# Filla_GPS_2015.net
KiCad netlist of a schematic drawn in EAGLE
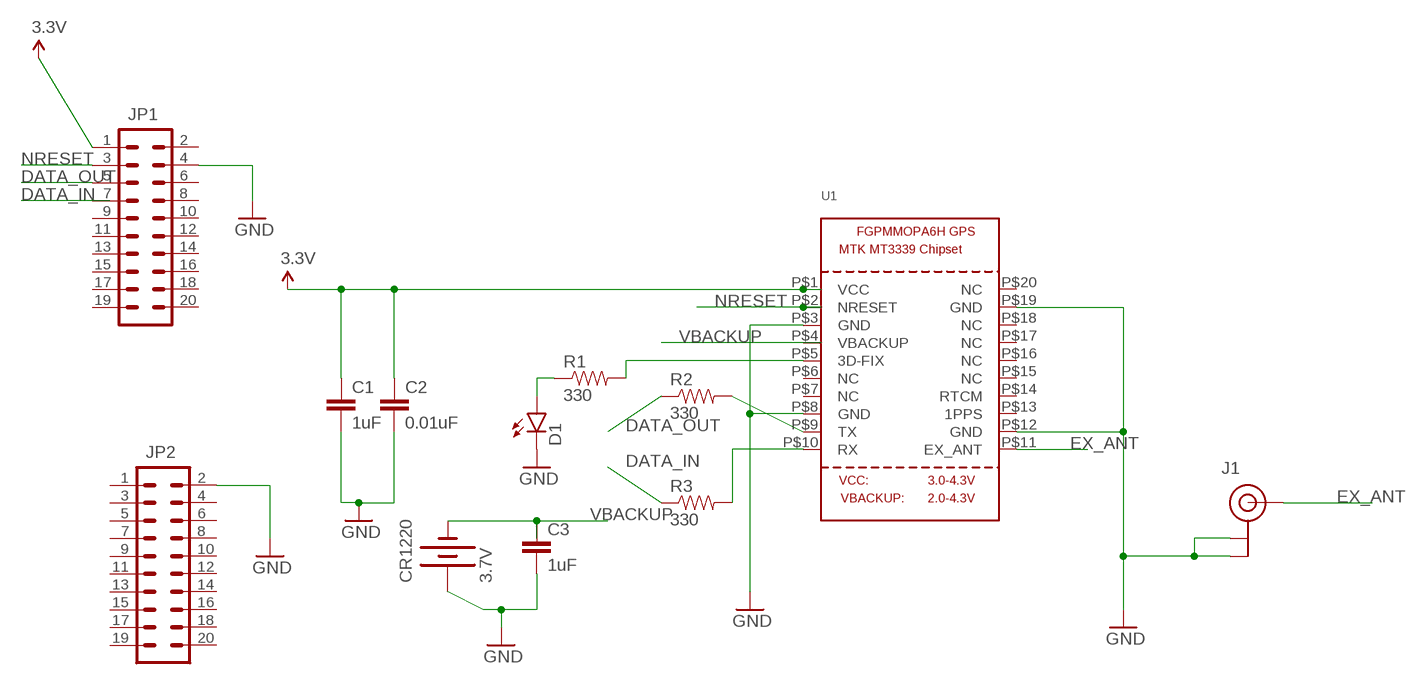
[diagram p0: schematic, sheet 1]

(export (version "E")
  (design (tool "Eeschema 10.0.6"))
  (components
    (comp (ref "C1")
      (value "1uF")
      (footprint "eagle-import:1206")
      (libsource (lib "eagle-import") (part "CAP1206"))
    )
    (comp (ref "C2")
      (value "0.01uF")
      (footprint "eagle-import:1206")
      (libsource (lib "eagle-import") (part "CAP1206"))
    )
    (comp (ref "C3")
      (value "1uF")
      (footprint "eagle-import:1206")
      (libsource (lib "eagle-import") (part "CAP1206"))
    )
    (comp (ref "CR1220")
      (value "3.7V")
      (footprint "eagle-import:BATTCON_12MM")
      (libsource (lib "eagle-import") (part "BATTERY12MM"))
    )
    (comp (ref "D1")
      (value "LED1206")
      (footprint "eagle-import:LED-1206")
      (libsource (lib "eagle-import") (part "LED1206"))
    )
    (comp (ref "J1")
      (value "U.FL")
      (footprint "eagle-import:U.FL")
      (libsource (lib "eagle-import") (part "U.FL"))
    )
    (comp (ref "JP1")
      (value "M10X2")
      (footprint "eagle-import:2X10")
      (libsource (lib "eagle-import") (part "M10X2"))
    )
    (comp (ref "JP2")
      (value "M10X2")
      (footprint "eagle-import:2X10")
      (libsource (lib "eagle-import") (part "M10X2"))
    )
    (comp (ref "R1")
      (value "330")
      (footprint "eagle-import:1206")
      (libsource (lib "eagle-import") (part "RESISTOR1206"))
    )
    (comp (ref "R2")
      (value "330")
      (footprint "eagle-import:1206")
      (libsource (lib "eagle-import") (part "RESISTOR1206"))
    )
    (comp (ref "R3")
      (value "330")
      (footprint "eagle-import:1206")
      (libsource (lib "eagle-import") (part "RESISTOR1206"))
    )
    (comp (ref "U1")
      (value "GPS_FGPMMOPA6H")
      (footprint "eagle-import:FGPMMOPA6H")
      (libsource (lib "eagle-import") (part "GPS_FGPMMOPA6H"))
    )
  )
  (nets
    (net (code "1") (name "/DATA_IN") (class "Default")
      (node (ref "R3") (pin "1") (pinfunction "1_1") (pintype "passive"))
    )
    (net (code "2") (name "/DATA_OUT") (class "Default")
      (node (ref "JP1") (pin "5") (pinfunction "5_5") (pintype "passive"))
      (node (ref "R2") (pin "1") (pinfunction "1_1") (pintype "passive"))
    )
    (net (code "3") (name "/EX_ANT") (class "Default")
      (node (ref "J1") (pin "P$3") (pinfunction "SIGNAL_P$3") (pintype "bidirectional"))
      (node (ref "U1") (pin "P$11") (pinfunction "EX_ANT_P$11") (pintype "bidirectional"))
    )
    (net (code "4") (name "/NRESET") (class "Default")
      (node (ref "JP1") (pin "3") (pinfunction "3_3") (pintype "passive"))
      (node (ref "U1") (pin "P$2") (pinfunction "NRESET_P$2") (pintype "bidirectional"))
    )
    (net (code "5") (name "/VBACKUP") (class "Default")
      (node (ref "C3") (pin "1") (pinfunction "1_1") (pintype "passive"))
      (node (ref "CR1220") (pin "GND") (pinfunction "-_GND") (pintype "power_in"))
    )
    (net (code "6") (name "3.3V") (class "Default")
      (node (ref "C1") (pin "1") (pinfunction "1_1") (pintype "passive"))
      (node (ref "C2") (pin "1") (pinfunction "1_1") (pintype "passive"))
      (node (ref "JP1") (pin "1") (pinfunction "1_1") (pintype "passive"))
      (node (ref "U1") (pin "P$1") (pinfunction "VCC_P$1") (pintype "bidirectional"))
    )
    (net (code "7") (name "GND") (class "Default")
      (node (ref "C1") (pin "2") (pinfunction "2_2") (pintype "passive"))
      (node (ref "C2") (pin "2") (pinfunction "2_2") (pintype "passive"))
      (node (ref "C3") (pin "2") (pinfunction "2_2") (pintype "passive"))
      (node (ref "CR1220") (pin "PWR@1") (pinfunction "+_PWR@1") (pintype "power_in"))
      (node (ref "D1") (pin "C") (pinfunction "C_C") (pintype "passive"))
      (node (ref "J1") (pin "P$1") (pinfunction "GND_P$1") (pintype "bidirectional"))
      (node (ref "J1") (pin "P$2") (pinfunction "GND_P$2") (pintype "bidirectional"))
      (node (ref "JP1") (pin "4") (pinfunction "4_4") (pintype "passive"))
      (node (ref "JP2") (pin "2") (pinfunction "2_2") (pintype "passive"))
      (node (ref "U1") (pin "P$12") (pinfunction "GND_P$12") (pintype "bidirectional"))
      (node (ref "U1") (pin "P$19") (pinfunction "GND_P$19") (pintype "bidirectional"))
      (node (ref "U1") (pin "P$3") (pinfunction "GND_P$3") (pintype "bidirectional"))
      (node (ref "U1") (pin "P$8") (pinfunction "GND_P$8") (pintype "bidirectional"))
    )
    (net (code "8") (name "Net-(D1-PadA)") (class "Default")
      (node (ref "D1") (pin "A") (pinfunction "A_A") (pintype "passive"))
      (node (ref "R1") (pin "1") (pinfunction "1_1") (pintype "passive"))
    )
    (net (code "9") (name "Net-(U1-3D-FIX)") (class "Default")
      (node (ref "R1") (pin "2") (pinfunction "2_2") (pintype "passive"))
      (node (ref "U1") (pin "P$5") (pinfunction "3D-FIX_P$5") (pintype "bidirectional"))
    )
    (net (code "10") (name "Net-(U1-RX)") (class "Default")
      (node (ref "R3") (pin "2") (pinfunction "2_2") (pintype "passive"))
      (node (ref "U1") (pin "P$10") (pinfunction "RX_P$10") (pintype "bidirectional"))
    )
    (net (code "11") (name "Net-(U1-TX)") (class "Default")
      (node (ref "R2") (pin "2") (pinfunction "2_2") (pintype "passive"))
      (node (ref "U1") (pin "P$9") (pinfunction "TX_P$9") (pintype "bidirectional"))
    )
    (net (code "12") (name "unconnected-(JP1-Pad2)") (class "Default")
      (node (ref "JP1") (pin "2") (pinfunction "2_2") (pintype "passive"))
    )
    (net (code "13") (name "unconnected-(JP1-Pad6)") (class "Default")
      (node (ref "JP1") (pin "6") (pinfunction "6_6") (pintype "passive"))
    )
    (net (code "14") (name "unconnected-(JP1-Pad7)") (class "Default")
      (node (ref "JP1") (pin "7") (pinfunction "7_7") (pintype "passive"))
    )
    (net (code "15") (name "unconnected-(JP1-Pad8)") (class "Default")
      (node (ref "JP1") (pin "8") (pinfunction "8_8") (pintype "passive"))
    )
    (net (code "16") (name "unconnected-(JP1-Pad9)") (class "Default")
      (node (ref "JP1") (pin "9") (pinfunction "9_9") (pintype "passive"))
    )
    (net (code "17") (name "unconnected-(JP1-Pad10)") (class "Default")
      (node (ref "JP1") (pin "10") (pinfunction "10_10") (pintype "passive"))
    )
    (net (code "18") (name "unconnected-(JP1-Pad11)") (class "Default")
      (node (ref "JP1") (pin "11") (pinfunction "11_11") (pintype "passive"))
    )
    (net (code "19") (name "unconnected-(JP1-Pad12)") (class "Default")
      (node (ref "JP1") (pin "12") (pinfunction "12_12") (pintype "passive"))
    )
    (net (code "20") (name "unconnected-(JP1-Pad13)") (class "Default")
      (node (ref "JP1") (pin "13") (pinfunction "13_13") (pintype "passive"))
    )
    (net (code "21") (name "unconnected-(JP1-Pad14)") (class "Default")
      (node (ref "JP1") (pin "14") (pinfunction "14_14") (pintype "passive"))
    )
    (net (code "22") (name "unconnected-(JP1-Pad15)") (class "Default")
      (node (ref "JP1") (pin "15") (pinfunction "15_15") (pintype "passive"))
    )
    (net (code "23") (name "unconnected-(JP1-Pad16)") (class "Default")
      (node (ref "JP1") (pin "16") (pinfunction "16_16") (pintype "passive"))
    )
    (net (code "24") (name "unconnected-(JP1-Pad17)") (class "Default")
      (node (ref "JP1") (pin "17") (pinfunction "17_17") (pintype "passive"))
    )
    (net (code "25") (name "unconnected-(JP1-Pad18)") (class "Default")
      (node (ref "JP1") (pin "18") (pinfunction "18_18") (pintype "passive"))
    )
    (net (code "26") (name "unconnected-(JP1-Pad19)") (class "Default")
      (node (ref "JP1") (pin "19") (pinfunction "19_19") (pintype "passive"))
    )
    (net (code "27") (name "unconnected-(JP1-Pad20)") (class "Default")
      (node (ref "JP1") (pin "20") (pinfunction "20_20") (pintype "passive"))
    )
    (net (code "28") (name "unconnected-(JP2-Pad1)") (class "Default")
      (node (ref "JP2") (pin "1") (pinfunction "1_1") (pintype "passive"))
    )
    (net (code "29") (name "unconnected-(JP2-Pad3)") (class "Default")
      (node (ref "JP2") (pin "3") (pinfunction "3_3") (pintype "passive"))
    )
    (net (code "30") (name "unconnected-(JP2-Pad4)") (class "Default")
      (node (ref "JP2") (pin "4") (pinfunction "4_4") (pintype "passive"))
    )
    (net (code "31") (name "unconnected-(JP2-Pad5)") (class "Default")
      (node (ref "JP2") (pin "5") (pinfunction "5_5") (pintype "passive"))
    )
    (net (code "32") (name "unconnected-(JP2-Pad6)") (class "Default")
      (node (ref "JP2") (pin "6") (pinfunction "6_6") (pintype "passive"))
    )
    (net (code "33") (name "unconnected-(JP2-Pad7)") (class "Default")
      (node (ref "JP2") (pin "7") (pinfunction "7_7") (pintype "passive"))
    )
    (net (code "34") (name "unconnected-(JP2-Pad8)") (class "Default")
      (node (ref "JP2") (pin "8") (pinfunction "8_8") (pintype "passive"))
    )
    (net (code "35") (name "unconnected-(JP2-Pad9)") (class "Default")
      (node (ref "JP2") (pin "9") (pinfunction "9_9") (pintype "passive"))
    )
    (net (code "36") (name "unconnected-(JP2-Pad10)") (class "Default")
      (node (ref "JP2") (pin "10") (pinfunction "10_10") (pintype "passive"))
    )
    (net (code "37") (name "unconnected-(JP2-Pad11)") (class "Default")
      (node (ref "JP2") (pin "11") (pinfunction "11_11") (pintype "passive"))
    )
    (net (code "38") (name "unconnected-(JP2-Pad12)") (class "Default")
      (node (ref "JP2") (pin "12") (pinfunction "12_12") (pintype "passive"))
    )
    (net (code "39") (name "unconnected-(JP2-Pad13)") (class "Default")
      (node (ref "JP2") (pin "13") (pinfunction "13_13") (pintype "passive"))
    )
    (net (code "40") (name "unconnected-(JP2-Pad14)") (class "Default")
      (node (ref "JP2") (pin "14") (pinfunction "14_14") (pintype "passive"))
    )
    (net (code "41") (name "unconnected-(JP2-Pad15)") (class "Default")
      (node (ref "JP2") (pin "15") (pinfunction "15_15") (pintype "passive"))
    )
    (net (code "42") (name "unconnected-(JP2-Pad16)") (class "Default")
      (node (ref "JP2") (pin "16") (pinfunction "16_16") (pintype "passive"))
    )
    (net (code "43") (name "unconnected-(JP2-Pad17)") (class "Default")
      (node (ref "JP2") (pin "17") (pinfunction "17_17") (pintype "passive"))
    )
    (net (code "44") (name "unconnected-(JP2-Pad18)") (class "Default")
      (node (ref "JP2") (pin "18") (pinfunction "18_18") (pintype "passive"))
    )
    (net (code "45") (name "unconnected-(JP2-Pad19)") (class "Default")
      (node (ref "JP2") (pin "19") (pinfunction "19_19") (pintype "passive"))
    )
    (net (code "46") (name "unconnected-(JP2-Pad20)") (class "Default")
      (node (ref "JP2") (pin "20") (pinfunction "20_20") (pintype "passive"))
    )
    (net (code "47") (name "unconnected-(U1-1PPS-PadP$13)") (class "Default")
      (node (ref "U1") (pin "P$13") (pinfunction "1PPS_P$13") (pintype "bidirectional"))
    )
    (net (code "48") (name "unconnected-(U1-NC-PadP$6)") (class "Default")
      (node (ref "U1") (pin "P$6") (pinfunction "NC_P$6") (pintype "bidirectional"))
    )
    (net (code "49") (name "unconnected-(U1-NC-PadP$7)") (class "Default")
      (node (ref "U1") (pin "P$7") (pinfunction "NC_P$7") (pintype "bidirectional"))
    )
    (net (code "50") (name "unconnected-(U1-NC-PadP$15)") (class "Default")
      (node (ref "U1") (pin "P$15") (pinfunction "NC_P$15") (pintype "bidirectional"))
    )
    (net (code "51") (name "unconnected-(U1-NC-PadP$16)") (class "Default")
      (node (ref "U1") (pin "P$16") (pinfunction "NC_P$16") (pintype "bidirectional"))
    )
    (net (code "52") (name "unconnected-(U1-NC-PadP$17)") (class "Default")
      (node (ref "U1") (pin "P$17") (pinfunction "NC_P$17") (pintype "bidirectional"))
    )
    (net (code "53") (name "unconnected-(U1-NC-PadP$18)") (class "Default")
      (node (ref "U1") (pin "P$18") (pinfunction "NC_P$18") (pintype "bidirectional"))
    )
    (net (code "54") (name "unconnected-(U1-NC-PadP$20)") (class "Default")
      (node (ref "U1") (pin "P$20") (pinfunction "NC_P$20") (pintype "bidirectional"))
    )
    (net (code "55") (name "unconnected-(U1-RTCM-PadP$14)") (class "Default")
      (node (ref "U1") (pin "P$14") (pinfunction "RTCM_P$14") (pintype "bidirectional"))
    )
    (net (code "56") (name "unconnected-(U1-VBACKUP-PadP$4)") (class "Default")
      (node (ref "U1") (pin "P$4") (pinfunction "VBACKUP_P$4") (pintype "bidirectional"))
    )
  )
)
